# V_Reg.net
KiCad netlist of a schematic drawn in Altium Designer
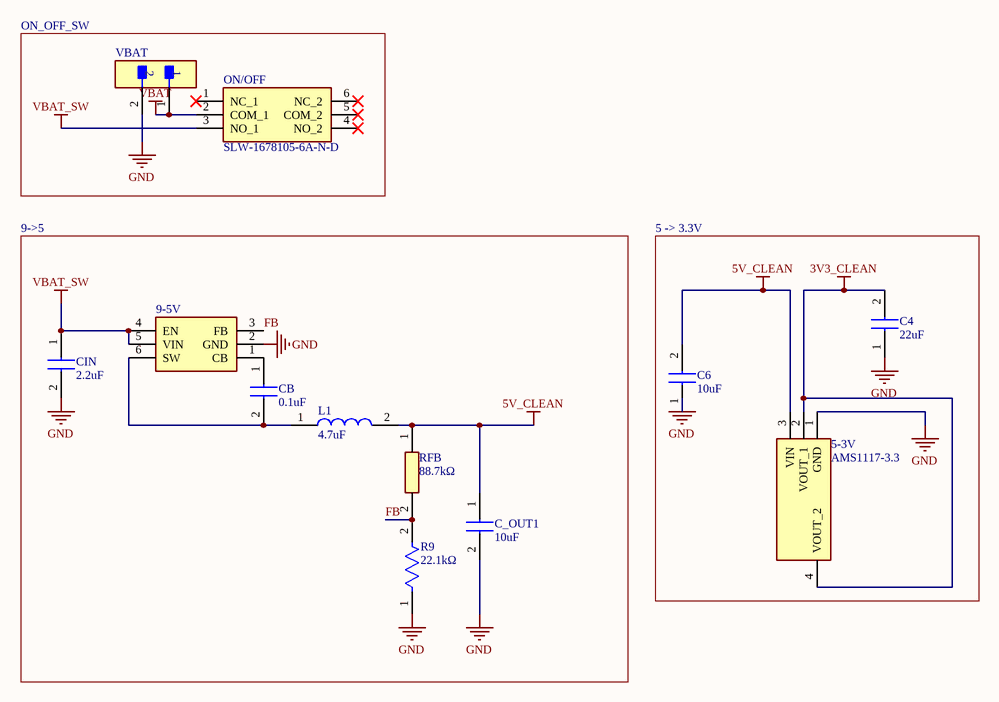
[diagram p0: V_Reg.SchDoc]

(export (version "E")
  (design (tool "Eeschema 10.0.6"))
  (components
    (comp (ref "5-3V")
      (value "AMS1117-3.3")
      (footprint "SamacSys:SOT229P700X180-4N")
      (description "Integrated Circuit")
      (libsource (lib "*") (part "AMS1117-3.3"))
    )
    (comp (ref "9-5V")
      (value "LMR50410Y5FQDBVRQ1")
      (footprint "SamacSys:SOT95P280X145-6N")
      (description "Integrated Circuit")
      (fields (field (name "MOUSER PART NUMBER") "595-R50410Y5FQDBVRQ1"))
      (libsource (lib "*") (part "LMR50410Y5FQDBVRQ1"))
    )
    (comp (ref "C4")
      (value "22uF")
      (footprint "SamacSys:CAPC1608X105N")
      (description "Capacitor")
      (fields
        (field (name "MANUFACTURER_PART_NUMBER") "CL10A226MP8NUNE")
        (field (name "MOUSER PART NUMBER") "187-CL10A226MP8NUNE")
      )
      (libsource (lib "*") (part "CL10A226MP8NUNE"))
    )
    (comp (ref "C6")
      (value "10uF")
      (footprint "SamacSys:CAPC3216X180N")
      (description "Capacitor")
      (fields
        (field (name "MANUFACTURER_PART_NUMBER") "CL31B106KAHNNNE")
        (field (name "MOUSER PART NUMBER") "187-CL31B106KAHNNNE")
      )
      (libsource (lib "*") (part "CL31B106KAHNNNE"))
    )
    (comp (ref "CB")
      (value "0.1uF")
      (footprint "SamacSys:CAPC1608X90N")
      (description "Capacitor")
      (fields
        (field (name "MANUFACTURER_PART_NUMBER") "CC0603KRX7R7BB104")
        (field (name "MOUSER PART NUMBER") "603-CC603KRX7R7BB104")
      )
      (libsource (lib "*") (part "CC0603KRX7R7BB104"))
    )
    (comp (ref "CIN")
      (value "2.2uF")
      (footprint "SamacSys:CAPC1608X90N")
      (description "Capacitor")
      (fields
        (field (name "MANUFACTURER_PART_NUMBER") "CL10A225KO8NNNC")
        (field (name "MOUSER PART NUMBER") "187-CL10A225KO8NNNC")
      )
      (libsource (lib "*") (part "CL10A225KO8NNNC"))
    )
    (comp (ref "C_OUT1")
      (value "10uF")
      (footprint "SamacSys:CAPC2012X140N")
      (description "Capacitor")
      (fields
        (field (name "MANUFACTURER_PART_NUMBER") "CL21B106KOQNNNE")
        (field (name "MOUSER PART NUMBER") "187-CL21B106KOQNNNE")
      )
      (libsource (lib "*") (part "CL21B106KOQNNNE"))
    )
    (comp (ref "L1")
      (value "4.7uF")
      (footprint "SamacSys:621767970")
      (description "Inductor")
      (fields (field (name "MANUFACTURER_PART_NUMBER") "7-2176797-1"))
      (libsource (lib "*") (part "7-2176797-1"))
    )
    (comp (ref "ON/OFF")
      (value "SLW-1678105-6A-N-D")
      (footprint "SamacSys:SLW16781056AND")
      (description "Switch")
      (fields (field (name "MOUSER PART NUMBER") "179-SLW16781056AND"))
      (libsource (lib "*") (part "SLW-1678105-6A-N-D"))
    )
    (comp (ref "R9")
      (value "22.1kΩ")
      (footprint "FP-RT0603-MFG")
      (description "RES 22.1K OHM 1/10W .1% SMD 0603")
      (fields
        (field (name "TOLERANCE") "0.001")
        (field (name "OCTOPART") "https://octopart.com/rt0603brd0722k1l-yageo-1430878")
      )
      (libsource (lib "Altium Content Vault") (part "1029c3af85768c4190bb7ad29bc67b5"))
    )
    (comp (ref "RFB")
      (value "88.7kΩ")
      (footprint "SamacSys:ERA3AEB101V")
      (description "Resistor")
      (fields
        (field (name "MANUFACTURER_PART_NUMBER") "ERA-3AEB8872V")
        (field (name "MOUSER PART NUMBER") "667-ERA-3AEB8872V")
      )
      (libsource (lib "*") (part "ERA-3AEB8872V"))
    )
    (comp (ref "VBAT")
      (value "837-22-002-30-001101")
      (footprint "FP-837-22-002-30-001101-MFG")
      (description "CONN SPRING PISTON 2POS SMD")
      (fields
        (field (name "MANUFACTURER") "Mill-Max")
        (field (name "OCTOPART") "https://octopart.com/837-22-002-30-001101-mill-max-76383858")
      )
      (libsource (lib "Altium Content Vault") (part "3bc925449376181038e59eaffc5286c"))
    )
  )
  (nets
    (net (code "1") (name "/FB") (class "Default")
      (node (ref "9-5V") (pin "3") (pinfunction "FB_3") (pintype "passive"))
      (node (ref "R9") (pin "2") (pinfunction "2_2") (pintype "passive"))
      (node (ref "RFB") (pin "2") (pinfunction "2_2") (pintype "passive"))
    )
    (net (code "2") (name "3V3_CLEAN") (class "Default")
      (node (ref "5-3V") (pin "2") (pinfunction "VOUT_1_2") (pintype "passive"))
      (node (ref "5-3V") (pin "4") (pinfunction "VOUT_2_4") (pintype "passive"))
      (node (ref "C4") (pin "2") (pinfunction "2_2") (pintype "passive"))
    )
    (net (code "3") (name "5V_CLEAN") (class "Default")
      (node (ref "5-3V") (pin "3") (pinfunction "VIN_3") (pintype "passive"))
      (node (ref "C6") (pin "2") (pinfunction "2_2") (pintype "passive"))
      (node (ref "C_OUT1") (pin "1") (pinfunction "1_1") (pintype "passive"))
      (node (ref "L1") (pin "2") (pinfunction "2_2") (pintype "passive"))
      (node (ref "RFB") (pin "1") (pinfunction "1_1") (pintype "passive"))
    )
    (net (code "4") (name "GND") (class "Default")
      (node (ref "5-3V") (pin "1") (pinfunction "GND_1") (pintype "passive"))
      (node (ref "9-5V") (pin "2") (pinfunction "GND_2") (pintype "power_in"))
      (node (ref "C4") (pin "1") (pinfunction "1_1") (pintype "passive"))
      (node (ref "C6") (pin "1") (pinfunction "1_1") (pintype "passive"))
      (node (ref "CIN") (pin "2") (pinfunction "2_2") (pintype "passive"))
      (node (ref "C_OUT1") (pin "2") (pinfunction "2_2") (pintype "passive"))
      (node (ref "R9") (pin "1") (pinfunction "1_1") (pintype "passive"))
      (node (ref "VBAT") (pin "2") (pinfunction "2_2") (pintype "passive"))
    )
    (net (code "5") (name "Net-(9-5V-CB)") (class "Default")
      (node (ref "9-5V") (pin "1") (pinfunction "CB_1") (pintype "passive"))
      (node (ref "CB") (pin "1") (pinfunction "1_1") (pintype "passive"))
    )
    (net (code "6") (name "Net-(9-5V-SW)") (class "Default")
      (node (ref "9-5V") (pin "6") (pinfunction "SW_6") (pintype "passive"))
      (node (ref "CB") (pin "2") (pinfunction "2_2") (pintype "passive"))
      (node (ref "L1") (pin "1") (pinfunction "1_1") (pintype "passive"))
    )
    (net (code "7") (name "VBAT") (class "Default")
      (node (ref "ON/OFF") (pin "2") (pinfunction "COM_1_2") (pintype "passive"))
      (node (ref "VBAT") (pin "1") (pinfunction "1_1") (pintype "passive"))
    )
    (net (code "8") (name "VBAT_SW") (class "Default")
      (node (ref "9-5V") (pin "4") (pinfunction "EN_4") (pintype "passive"))
      (node (ref "9-5V") (pin "5") (pinfunction "VIN_5") (pintype "power_in"))
      (node (ref "CIN") (pin "1") (pinfunction "1_1") (pintype "passive"))
      (node (ref "ON/OFF") (pin "3") (pinfunction "NO_1_3") (pintype "passive"))
    )
    (net (code "9") (name "unconnected-(ON/OFF-COM_2-Pad5)") (class "Default")
      (node (ref "ON/OFF") (pin "5") (pinfunction "COM_2_5") (pintype "passive+no_connect"))
    )
    (net (code "10") (name "unconnected-(ON/OFF-NC_1-Pad1)") (class "Default")
      (node (ref "ON/OFF") (pin "1") (pinfunction "NC_1_1") (pintype "passive+no_connect"))
    )
    (net (code "11") (name "unconnected-(ON/OFF-NC_2-Pad6)") (class "Default")
      (node (ref "ON/OFF") (pin "6") (pinfunction "NC_2_6") (pintype "passive+no_connect"))
    )
    (net (code "12") (name "unconnected-(ON/OFF-NO_2-Pad4)") (class "Default")
      (node (ref "ON/OFF") (pin "4") (pinfunction "NO_2_4") (pintype "passive+no_connect"))
    )
  )
)
